# Power_Monitoring_Circuts.net
KiCad netlist of a schematic drawn in EAGLE
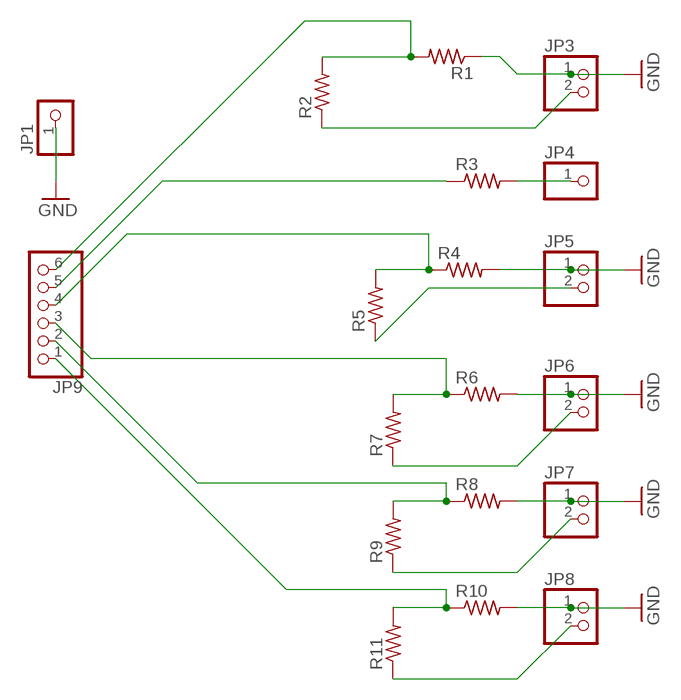
[diagram p0: schematic, sheet 1]

(export (version "E")
  (design (tool "Eeschema 10.0.6"))
  (components
    (comp (ref "JP1")
      (value "PINHD-1X1")
      (footprint "eagle-import:1X01")
      (libsource (lib "eagle-import") (part "PINHD-1X1"))
    )
    (comp (ref "JP3")
      (value "PINHD-1X2")
      (footprint "eagle-import:1X02")
      (libsource (lib "eagle-import") (part "PINHD-1X2"))
    )
    (comp (ref "JP4")
      (value "PINHD-1X1")
      (footprint "eagle-import:1X01")
      (libsource (lib "eagle-import") (part "PINHD-1X1"))
    )
    (comp (ref "JP5")
      (value "PINHD-1X2")
      (footprint "eagle-import:1X02")
      (libsource (lib "eagle-import") (part "PINHD-1X2"))
    )
    (comp (ref "JP6")
      (value "PINHD-1X2")
      (footprint "eagle-import:1X02")
      (libsource (lib "eagle-import") (part "PINHD-1X2"))
    )
    (comp (ref "JP7")
      (value "PINHD-1X2")
      (footprint "eagle-import:1X02")
      (libsource (lib "eagle-import") (part "PINHD-1X2"))
    )
    (comp (ref "JP8")
      (value "PINHD-1X2")
      (footprint "eagle-import:1X02")
      (libsource (lib "eagle-import") (part "PINHD-1X2"))
    )
    (comp (ref "JP9")
      (value "PINHD-1X6")
      (footprint "eagle-import:1X06")
      (libsource (lib "eagle-import") (part "PINHD-1X6"))
    )
    (comp (ref "R1")
      (value "R-US_0204/7")
      (footprint "eagle-import:0204_7")
      (libsource (lib "eagle-import") (part "R-US_0204/7"))
    )
    (comp (ref "R2")
      (value "R-US_0204/7")
      (footprint "eagle-import:0204_7")
      (libsource (lib "eagle-import") (part "R-US_0204/7"))
    )
    (comp (ref "R3")
      (value "R-US_0204/7")
      (footprint "eagle-import:0204_7")
      (libsource (lib "eagle-import") (part "R-US_0204/7"))
    )
    (comp (ref "R4")
      (value "R-US_0204/7")
      (footprint "eagle-import:0204_7")
      (libsource (lib "eagle-import") (part "R-US_0204/7"))
    )
    (comp (ref "R5")
      (value "R-US_0204/7")
      (footprint "eagle-import:0204_7")
      (libsource (lib "eagle-import") (part "R-US_0204/7"))
    )
    (comp (ref "R6")
      (value "R-US_0204/7")
      (footprint "eagle-import:0204_7")
      (libsource (lib "eagle-import") (part "R-US_0204/7"))
    )
    (comp (ref "R7")
      (value "R-US_0204/7")
      (footprint "eagle-import:0204_7")
      (libsource (lib "eagle-import") (part "R-US_0204/7"))
    )
    (comp (ref "R8")
      (value "R-US_0204/7")
      (footprint "eagle-import:0204_7")
      (libsource (lib "eagle-import") (part "R-US_0204/7"))
    )
    (comp (ref "R9")
      (value "R-US_0204/7")
      (footprint "eagle-import:0204_7")
      (libsource (lib "eagle-import") (part "R-US_0204/7"))
    )
    (comp (ref "R10")
      (value "R-US_0204/7")
      (footprint "eagle-import:0204_7")
      (libsource (lib "eagle-import") (part "R-US_0204/7"))
    )
    (comp (ref "R11")
      (value "R-US_0204/7")
      (footprint "eagle-import:0204_7")
      (libsource (lib "eagle-import") (part "R-US_0204/7"))
    )
  )
  (nets
    (net (code "1") (name "GND") (class "Default")
      (node (ref "JP1") (pin "1") (pinfunction "1_1") (pintype "passive"))
      (node (ref "JP3") (pin "1") (pinfunction "1_1") (pintype "passive"))
      (node (ref "JP5") (pin "1") (pinfunction "1_1") (pintype "passive"))
      (node (ref "JP6") (pin "1") (pinfunction "1_1") (pintype "passive"))
      (node (ref "JP7") (pin "1") (pinfunction "1_1") (pintype "passive"))
      (node (ref "JP8") (pin "1") (pinfunction "1_1") (pintype "passive"))
      (node (ref "R1") (pin "1") (pinfunction "1_1") (pintype "passive"))
      (node (ref "R10") (pin "2") (pinfunction "2_2") (pintype "passive"))
      (node (ref "R4") (pin "2") (pinfunction "2_2") (pintype "passive"))
      (node (ref "R6") (pin "2") (pinfunction "2_2") (pintype "passive"))
      (node (ref "R8") (pin "2") (pinfunction "2_2") (pintype "passive"))
    )
    (net (code "2") (name "Net-(JP3-Pad2)") (class "Default")
      (node (ref "JP3") (pin "2") (pinfunction "2_2") (pintype "passive"))
      (node (ref "R2") (pin "1") (pinfunction "1_1") (pintype "passive"))
    )
    (net (code "3") (name "Net-(JP4-Pad1)") (class "Default")
      (node (ref "JP4") (pin "1") (pinfunction "1_1") (pintype "passive"))
      (node (ref "R3") (pin "2") (pinfunction "2_2") (pintype "passive"))
    )
    (net (code "4") (name "Net-(JP5-Pad2)") (class "Default")
      (node (ref "JP5") (pin "2") (pinfunction "2_2") (pintype "passive"))
      (node (ref "R5") (pin "1") (pinfunction "1_1") (pintype "passive"))
    )
    (net (code "5") (name "Net-(JP6-Pad2)") (class "Default")
      (node (ref "JP6") (pin "2") (pinfunction "2_2") (pintype "passive"))
      (node (ref "R7") (pin "1") (pinfunction "1_1") (pintype "passive"))
    )
    (net (code "6") (name "Net-(JP7-Pad2)") (class "Default")
      (node (ref "JP7") (pin "2") (pinfunction "2_2") (pintype "passive"))
      (node (ref "R9") (pin "1") (pinfunction "1_1") (pintype "passive"))
    )
    (net (code "7") (name "Net-(JP8-Pad2)") (class "Default")
      (node (ref "JP8") (pin "2") (pinfunction "2_2") (pintype "passive"))
      (node (ref "R11") (pin "1") (pinfunction "1_1") (pintype "passive"))
    )
    (net (code "8") (name "Net-(JP9-Pad1)") (class "Default")
      (node (ref "JP9") (pin "1") (pinfunction "1_1") (pintype "passive"))
      (node (ref "R10") (pin "1") (pinfunction "1_1") (pintype "passive"))
      (node (ref "R11") (pin "2") (pinfunction "2_2") (pintype "passive"))
    )
    (net (code "9") (name "Net-(JP9-Pad2)") (class "Default")
      (node (ref "JP9") (pin "2") (pinfunction "2_2") (pintype "passive"))
      (node (ref "R8") (pin "1") (pinfunction "1_1") (pintype "passive"))
      (node (ref "R9") (pin "2") (pinfunction "2_2") (pintype "passive"))
    )
    (net (code "10") (name "Net-(JP9-Pad3)") (class "Default")
      (node (ref "JP9") (pin "3") (pinfunction "3_3") (pintype "passive"))
      (node (ref "R6") (pin "1") (pinfunction "1_1") (pintype "passive"))
      (node (ref "R7") (pin "2") (pinfunction "2_2") (pintype "passive"))
    )
    (net (code "11") (name "Net-(JP9-Pad4)") (class "Default")
      (node (ref "JP9") (pin "4") (pinfunction "4_4") (pintype "passive"))
      (node (ref "R4") (pin "1") (pinfunction "1_1") (pintype "passive"))
      (node (ref "R5") (pin "2") (pinfunction "2_2") (pintype "passive"))
    )
    (net (code "12") (name "Net-(JP9-Pad5)") (class "Default")
      (node (ref "JP9") (pin "5") (pinfunction "5_5") (pintype "passive"))
      (node (ref "R3") (pin "1") (pinfunction "1_1") (pintype "passive"))
    )
    (net (code "13") (name "Net-(JP9-Pad6)") (class "Default")
      (node (ref "JP9") (pin "6") (pinfunction "6_6") (pintype "passive"))
      (node (ref "R1") (pin "2") (pinfunction "2_2") (pintype "passive"))
      (node (ref "R2") (pin "2") (pinfunction "2_2") (pintype "passive"))
    )
  )
)
